# misc_sensors.net
KiCad netlist of a schematic drawn in Altium Designer
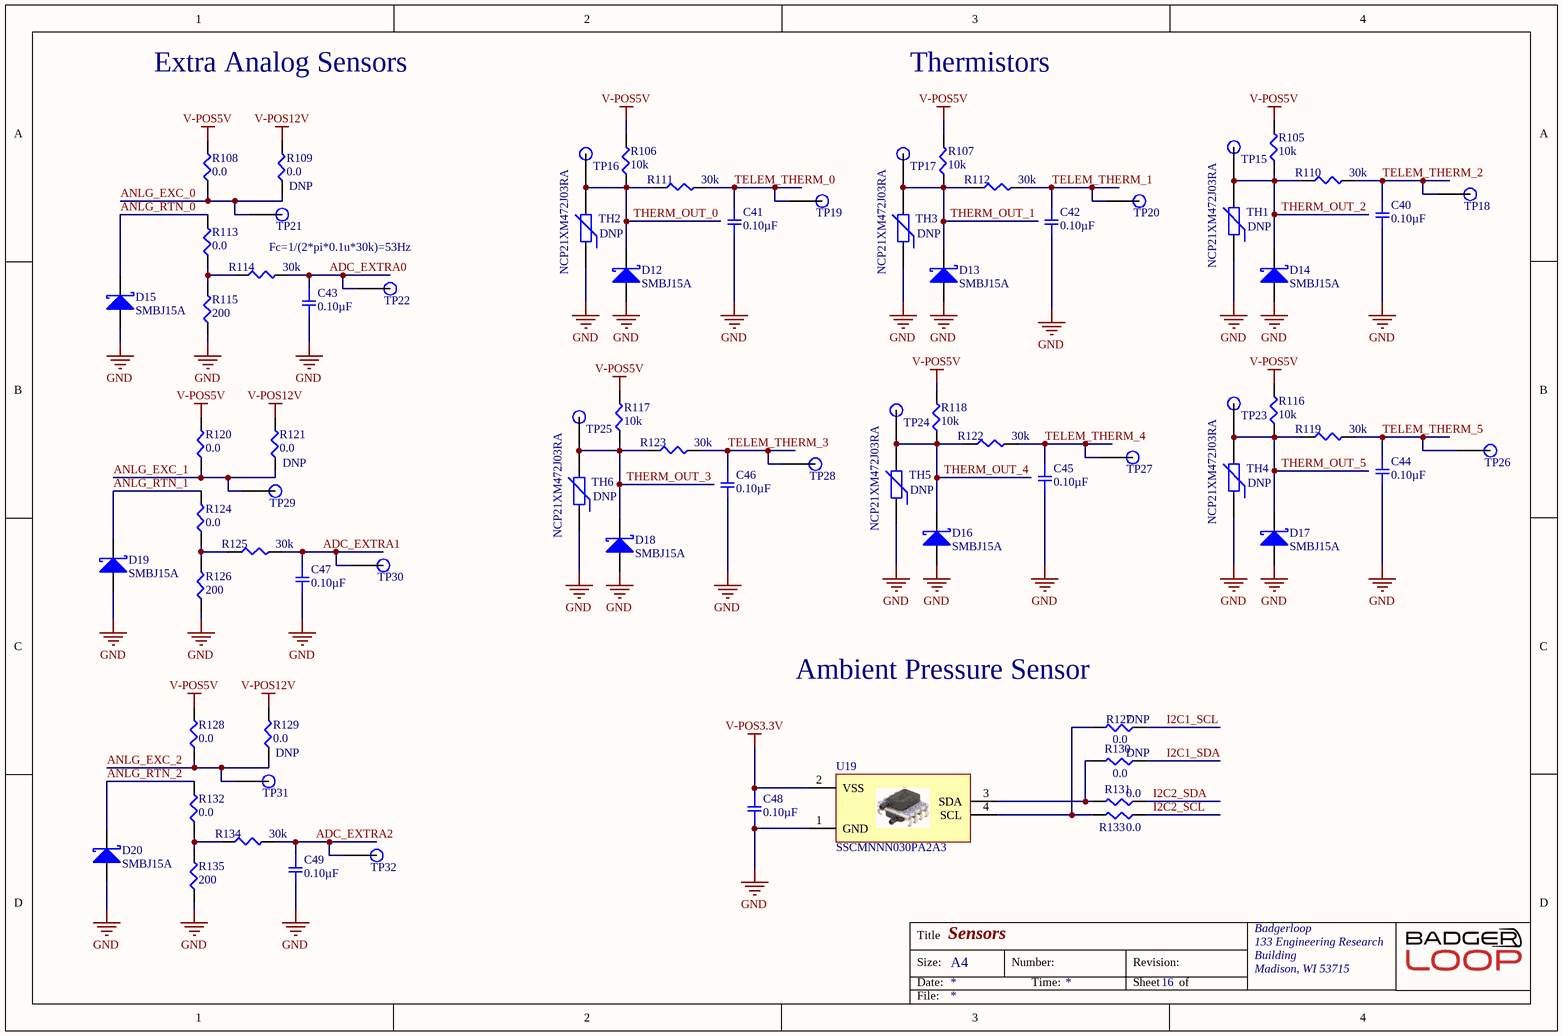
[diagram p0: misc_sensors.SchDoc]

(export (version "E")
  (design (tool "Eeschema 10.0.6"))
  (components
    (comp (ref "C40")
      (value "0.10µF")
      (footprint "SMD-0805C")
      (description "CAP CER 0.1UF 16V X7R 0805")
      (fields
        (field (name "DIGI-KEY PART NUMBER") "490-1683-1-ND")
        (field (name "PART NUMBER") "GRM219R71C104KA01D")
      )
      (libsource (lib "capacitors") (part "GRM219R71C104KA01D"))
    )
    (comp (ref "C41")
      (value "0.10µF")
      (footprint "SMD-0805C")
      (description "CAP CER 0.1UF 16V X7R 0805")
      (fields
        (field (name "DIGI-KEY PART NUMBER") "490-1683-1-ND")
        (field (name "PART NUMBER") "GRM219R71C104KA01D")
      )
      (libsource (lib "capacitors") (part "GRM219R71C104KA01D"))
    )
    (comp (ref "C42")
      (value "0.10µF")
      (footprint "SMD-0805C")
      (description "CAP CER 0.1UF 16V X7R 0805")
      (fields
        (field (name "DIGI-KEY PART NUMBER") "490-1683-1-ND")
        (field (name "PART NUMBER") "GRM219R71C104KA01D")
      )
      (libsource (lib "capacitors") (part "GRM219R71C104KA01D"))
    )
    (comp (ref "C43")
      (value "0.10µF")
      (footprint "SMD-0805C")
      (description "CAP CER 0.1UF 25V X7R 0805")
      (fields
        (field (name "DIGI-KEY PART NUMBER") "490-12754-1-ND")
        (field (name "PART NUMBER") "GRM219R71E104KA01D")
      )
      (libsource (lib "capacitors") (part "GRM219R71E104KA01D"))
    )
    (comp (ref "C44")
      (value "0.10µF")
      (footprint "SMD-0805C")
      (description "CAP CER 0.1UF 16V X7R 0805")
      (fields
        (field (name "DIGI-KEY PART NUMBER") "490-1683-1-ND")
        (field (name "PART NUMBER") "GRM219R71C104KA01D")
      )
      (libsource (lib "capacitors") (part "GRM219R71C104KA01D"))
    )
    (comp (ref "C45")
      (value "0.10µF")
      (footprint "SMD-0805C")
      (description "CAP CER 0.1UF 16V X7R 0805")
      (fields
        (field (name "DIGI-KEY PART NUMBER") "490-1683-1-ND")
        (field (name "PART NUMBER") "GRM219R71C104KA01D")
      )
      (libsource (lib "capacitors") (part "GRM219R71C104KA01D"))
    )
    (comp (ref "C46")
      (value "0.10µF")
      (footprint "SMD-0805C")
      (description "CAP CER 0.1UF 16V X7R 0805")
      (fields
        (field (name "DIGI-KEY PART NUMBER") "490-1683-1-ND")
        (field (name "PART NUMBER") "GRM219R71C104KA01D")
      )
      (libsource (lib "capacitors") (part "GRM219R71C104KA01D"))
    )
    (comp (ref "C47")
      (value "0.10µF")
      (footprint "SMD-0805C")
      (description "CAP CER 0.1UF 25V X7R 0805")
      (fields
        (field (name "DIGI-KEY PART NUMBER") "490-12754-1-ND")
        (field (name "PART NUMBER") "GRM219R71E104KA01D")
      )
      (libsource (lib "capacitors") (part "GRM219R71E104KA01D"))
    )
    (comp (ref "C48")
      (value "0.10µF")
      (footprint "SMD-0805C")
      (description "CAP CER 0.1UF 25V X7R 0805")
      (fields
        (field (name "DIGI-KEY PART NUMBER") "490-12754-1-ND")
        (field (name "PART NUMBER") "GRM219R71E104KA01D")
      )
      (libsource (lib "capacitors") (part "GRM219R71E104KA01D"))
    )
    (comp (ref "C49")
      (value "0.10µF")
      (footprint "SMD-0805C")
      (description "CAP CER 0.1UF 25V X7R 0805")
      (fields
        (field (name "DIGI-KEY PART NUMBER") "490-12754-1-ND")
        (field (name "PART NUMBER") "GRM219R71E104KA01D")
      )
      (libsource (lib "capacitors") (part "GRM219R71E104KA01D"))
    )
    (comp (ref "D12")
      (value "SMBJ15A")
      (footprint "DIOM4436X26N")
      (description "TVS DIODE 15V 24.4V DO214AA")
      (fields (field (name "MANUFACTURER") "Littelfuse") (field (name "VOLTAGE") "5V"))
      (libsource (lib "misc") (part "SMBJ15A"))
    )
    (comp (ref "D13")
      (value "SMBJ15A")
      (footprint "DIOM4436X26N")
      (description "TVS DIODE 15V 24.4V DO214AA")
      (fields (field (name "MANUFACTURER") "Littelfuse") (field (name "VOLTAGE") "5V"))
      (libsource (lib "misc") (part "SMBJ15A"))
    )
    (comp (ref "D14")
      (value "SMBJ15A")
      (footprint "DIOM4436X26N")
      (description "TVS DIODE 15V 24.4V DO214AA")
      (fields (field (name "MANUFACTURER") "Littelfuse") (field (name "VOLTAGE") "5V"))
      (libsource (lib "misc") (part "SMBJ15A"))
    )
    (comp (ref "D15")
      (value "SMBJ15A")
      (footprint "DIOM4436X26N")
      (description "TVS DIODE 15V 24.4V DO214AA")
      (fields (field (name "MANUFACTURER") "Littelfuse") (field (name "VOLTAGE") "5V"))
      (libsource (lib "misc") (part "SMBJ15A"))
    )
    (comp (ref "D16")
      (value "SMBJ15A")
      (footprint "DIOM4436X26N")
      (description "TVS DIODE 15V 24.4V DO214AA")
      (fields (field (name "MANUFACTURER") "Littelfuse") (field (name "VOLTAGE") "5V"))
      (libsource (lib "misc") (part "SMBJ15A"))
    )
    (comp (ref "D17")
      (value "SMBJ15A")
      (footprint "DIOM4436X26N")
      (description "TVS DIODE 15V 24.4V DO214AA")
      (fields (field (name "MANUFACTURER") "Littelfuse") (field (name "VOLTAGE") "5V"))
      (libsource (lib "misc") (part "SMBJ15A"))
    )
    (comp (ref "D18")
      (value "SMBJ15A")
      (footprint "DIOM4436X26N")
      (description "TVS DIODE 15V 24.4V DO214AA")
      (fields (field (name "MANUFACTURER") "Littelfuse") (field (name "VOLTAGE") "5V"))
      (libsource (lib "misc") (part "SMBJ15A"))
    )
    (comp (ref "D19")
      (value "SMBJ15A")
      (footprint "DIOM4436X26N")
      (description "TVS DIODE 15V 24.4V DO214AA")
      (fields (field (name "MANUFACTURER") "Littelfuse") (field (name "VOLTAGE") "5V"))
      (libsource (lib "misc") (part "SMBJ15A"))
    )
    (comp (ref "D20")
      (value "SMBJ15A")
      (footprint "DIOM4436X26N")
      (description "TVS DIODE 15V 24.4V DO214AA")
      (fields (field (name "MANUFACTURER") "Littelfuse") (field (name "VOLTAGE") "5V"))
      (libsource (lib "misc") (part "SMBJ15A"))
    )
    (comp (ref "R105")
      (value "10k")
      (footprint "SMD-0805-RES")
      (description "RES SMD 10K OHM 1% 1/2W 0805")
      (fields
        (field (name "PART NUMBER") "ERJ-P06F1002V")
        (field (name "DIGI-KEY PART NUMBER") "P16059CT-ND")
      )
      (libsource (lib "resistors") (part "ERJ-P06F1002V"))
    )
    (comp (ref "R106")
      (value "10k")
      (footprint "SMD-0805-RES")
      (description "RES SMD 10K OHM 1% 1/2W 0805")
      (fields
        (field (name "PART NUMBER") "ERJ-P06F1002V")
        (field (name "DIGI-KEY PART NUMBER") "P16059CT-ND")
      )
      (libsource (lib "resistors") (part "ERJ-P06F1002V"))
    )
    (comp (ref "R107")
      (value "10k")
      (footprint "SMD-0805-RES")
      (description "RES SMD 10K OHM 1% 1/2W 0805")
      (fields
        (field (name "PART NUMBER") "ERJ-P06F1002V")
        (field (name "DIGI-KEY PART NUMBER") "P16059CT-ND")
      )
      (libsource (lib "resistors") (part "ERJ-P06F1002V"))
    )
    (comp (ref "R108")
      (value "0.0")
      (footprint "SMD-0805-RES")
      (description "RES SMD 0.0 OHM JUMPER 1/8W 0805")
      (fields (field (name "PART NUMBER") "ERJ-6GEY0R00V") (field (name "DIGI-KEY PART NUMBER") "P0.0ACT-ND"))
      (libsource (lib "resistors") (part "ERJ-6GEY0R00V"))
    )
    (comp (ref "R109")
      (value "0.0")
      (footprint "SMD-0805-RES")
      (description "RES SMD 0.0 OHM JUMPER 1/8W 0805")
      (fields
        (field (name "PART NUMBER") "ERJ-6GEY0R00V")
        (field (name "DIGI-KEY PART NUMBER") "P0.0ACT-ND")
        (field (name "DNP") "DNP")
      )
      (libsource (lib "resistors") (part "ERJ-6GEY0R00V"))
    )
    (comp (ref "R110")
      (value "30k")
      (footprint "SMD-0805-RES")
      (description "RES SMD 30K OHM 1% 1/8W 0805")
      (fields
        (field (name "PART NUMBER") "ERJ-6ENF3002V")
        (field (name "DIGI-KEY PART NUMBER") "P30.0KCCT-ND")
      )
      (libsource (lib "resistors") (part "ERJ-6ENF3002V"))
    )
    (comp (ref "R111")
      (value "30k")
      (footprint "SMD-0805-RES")
      (description "RES SMD 30K OHM 1% 1/8W 0805")
      (fields
        (field (name "PART NUMBER") "ERJ-6ENF3002V")
        (field (name "DIGI-KEY PART NUMBER") "P30.0KCCT-ND")
      )
      (libsource (lib "resistors") (part "ERJ-6ENF3002V"))
    )
    (comp (ref "R112")
      (value "30k")
      (footprint "SMD-0805-RES")
      (description "RES SMD 30K OHM 1% 1/8W 0805")
      (fields
        (field (name "PART NUMBER") "ERJ-6ENF3002V")
        (field (name "DIGI-KEY PART NUMBER") "P30.0KCCT-ND")
      )
      (libsource (lib "resistors") (part "ERJ-6ENF3002V"))
    )
    (comp (ref "R113")
      (value "0.0")
      (footprint "SMD-0805-RES")
      (description "RES SMD 0.0 OHM JUMPER 1/8W 0805")
      (fields (field (name "PART NUMBER") "ERJ-6GEY0R00V") (field (name "DIGI-KEY PART NUMBER") "P0.0ACT-ND"))
      (libsource (lib "resistors") (part "ERJ-6GEY0R00V"))
    )
    (comp (ref "R114")
      (value "30k")
      (footprint "SMD-0805-RES")
      (description "RES SMD 30K OHM 1% 1/8W 0805")
      (fields
        (field (name "PART NUMBER") "ERJ-6ENF3002V")
        (field (name "DIGI-KEY PART NUMBER") "P30.0KCCT-ND")
      )
      (libsource (lib "resistors") (part "ERJ-6ENF3002V"))
    )
    (comp (ref "R115")
      (value "200")
      (footprint "SMD-0805-RES")
      (description "RES SMD 200 OHM 1% 1/2W 0805")
      (fields
        (field (name "PART NUMBER") "ERJ-P06F2000V")
        (field (name "DIGI-KEY PART NUMBER") "P16064CT-ND")
      )
      (libsource (lib "resistors") (part "ERJ-P06F2000V"))
    )
    (comp (ref "R116")
      (value "10k")
      (footprint "SMD-0805-RES")
      (description "RES SMD 10K OHM 1% 1/2W 0805")
      (fields
        (field (name "PART NUMBER") "ERJ-P06F1002V")
        (field (name "DIGI-KEY PART NUMBER") "P16059CT-ND")
      )
      (libsource (lib "resistors") (part "ERJ-P06F1002V"))
    )
    (comp (ref "R117")
      (value "10k")
      (footprint "SMD-0805-RES")
      (description "RES SMD 10K OHM 1% 1/2W 0805")
      (fields
        (field (name "PART NUMBER") "ERJ-P06F1002V")
        (field (name "DIGI-KEY PART NUMBER") "P16059CT-ND")
      )
      (libsource (lib "resistors") (part "ERJ-P06F1002V"))
    )
    (comp (ref "R118")
      (value "10k")
      (footprint "SMD-0805-RES")
      (description "RES SMD 10K OHM 1% 1/2W 0805")
      (fields
        (field (name "PART NUMBER") "ERJ-P06F1002V")
        (field (name "DIGI-KEY PART NUMBER") "P16059CT-ND")
      )
      (libsource (lib "resistors") (part "ERJ-P06F1002V"))
    )
    (comp (ref "R119")
      (value "30k")
      (footprint "SMD-0805-RES")
      (description "RES SMD 30K OHM 1% 1/8W 0805")
      (fields
        (field (name "PART NUMBER") "ERJ-6ENF3002V")
        (field (name "DIGI-KEY PART NUMBER") "P30.0KCCT-ND")
      )
      (libsource (lib "resistors") (part "ERJ-6ENF3002V"))
    )
    (comp (ref "R120")
      (value "0.0")
      (footprint "SMD-0805-RES")
      (description "RES SMD 0.0 OHM JUMPER 1/8W 0805")
      (fields (field (name "PART NUMBER") "ERJ-6GEY0R00V") (field (name "DIGI-KEY PART NUMBER") "P0.0ACT-ND"))
      (libsource (lib "resistors") (part "ERJ-6GEY0R00V"))
    )
    (comp (ref "R121")
      (value "0.0")
      (footprint "SMD-0805-RES")
      (description "RES SMD 0.0 OHM JUMPER 1/8W 0805")
      (fields
        (field (name "PART NUMBER") "ERJ-6GEY0R00V")
        (field (name "DIGI-KEY PART NUMBER") "P0.0ACT-ND")
        (field (name "DNP") "DNP")
      )
      (libsource (lib "resistors") (part "ERJ-6GEY0R00V"))
    )
    (comp (ref "R122")
      (value "30k")
      (footprint "SMD-0805-RES")
      (description "RES SMD 30K OHM 1% 1/8W 0805")
      (fields
        (field (name "PART NUMBER") "ERJ-6ENF3002V")
        (field (name "DIGI-KEY PART NUMBER") "P30.0KCCT-ND")
      )
      (libsource (lib "resistors") (part "ERJ-6ENF3002V"))
    )
    (comp (ref "R123")
      (value "30k")
      (footprint "SMD-0805-RES")
      (description "RES SMD 30K OHM 1% 1/8W 0805")
      (fields
        (field (name "PART NUMBER") "ERJ-6ENF3002V")
        (field (name "DIGI-KEY PART NUMBER") "P30.0KCCT-ND")
      )
      (libsource (lib "resistors") (part "ERJ-6ENF3002V"))
    )
    (comp (ref "R124")
      (value "0.0")
      (footprint "SMD-0805-RES")
      (description "RES SMD 0.0 OHM JUMPER 1/8W 0805")
      (fields (field (name "PART NUMBER") "ERJ-6GEY0R00V") (field (name "DIGI-KEY PART NUMBER") "P0.0ACT-ND"))
      (libsource (lib "resistors") (part "ERJ-6GEY0R00V"))
    )
    (comp (ref "R125")
      (value "30k")
      (footprint "SMD-0805-RES")
      (description "RES SMD 30K OHM 1% 1/8W 0805")
      (fields
        (field (name "PART NUMBER") "ERJ-6ENF3002V")
        (field (name "DIGI-KEY PART NUMBER") "P30.0KCCT-ND")
      )
      (libsource (lib "resistors") (part "ERJ-6ENF3002V"))
    )
    (comp (ref "R126")
      (value "200")
      (footprint "SMD-0805-RES")
      (description "RES SMD 200 OHM 1% 1/2W 0805")
      (fields
        (field (name "PART NUMBER") "ERJ-P06F2000V")
        (field (name "DIGI-KEY PART NUMBER") "P16064CT-ND")
      )
      (libsource (lib "resistors") (part "ERJ-P06F2000V"))
    )
    (comp (ref "R127")
      (value "0.0")
      (footprint "SMD-0805-RES")
      (description "RES SMD 0.0 OHM JUMPER 1/8W 0805")
      (fields
        (field (name "PART NUMBER") "ERJ-6GEY0R00V")
        (field (name "DIGI-KEY PART NUMBER") "P0.0ACT-ND")
        (field (name "DNP") "DNP")
      )
      (libsource (lib "resistors") (part "ERJ-6GEY0R00V"))
    )
    (comp (ref "R128")
      (value "0.0")
      (footprint "SMD-0805-RES")
      (description "RES SMD 0.0 OHM JUMPER 1/8W 0805")
      (fields (field (name "PART NUMBER") "ERJ-6GEY0R00V") (field (name "DIGI-KEY PART NUMBER") "P0.0ACT-ND"))
      (libsource (lib "resistors") (part "ERJ-6GEY0R00V"))
    )
    (comp (ref "R129")
      (value "0.0")
      (footprint "SMD-0805-RES")
      (description "RES SMD 0.0 OHM JUMPER 1/8W 0805")
      (fields
        (field (name "PART NUMBER") "ERJ-6GEY0R00V")
        (field (name "DIGI-KEY PART NUMBER") "P0.0ACT-ND")
        (field (name "DNP") "DNP")
      )
      (libsource (lib "resistors") (part "ERJ-6GEY0R00V"))
    )
    (comp (ref "R130")
      (value "0.0")
      (footprint "SMD-0805-RES")
      (description "RES SMD 0.0 OHM JUMPER 1/8W 0805")
      (fields
        (field (name "PART NUMBER") "ERJ-6GEY0R00V")
        (field (name "DIGI-KEY PART NUMBER") "P0.0ACT-ND")
        (field (name "DNP") "DNP")
      )
      (libsource (lib "resistors") (part "ERJ-6GEY0R00V"))
    )
    (comp (ref "R131")
      (value "0.0")
      (footprint "SMD-0805-RES")
      (description "RES SMD 0.0 OHM JUMPER 1/8W 0805")
      (fields (field (name "PART NUMBER") "ERJ-6GEY0R00V") (field (name "DIGI-KEY PART NUMBER") "P0.0ACT-ND"))
      (libsource (lib "resistors") (part "ERJ-6GEY0R00V"))
    )
    (comp (ref "R132")
      (value "0.0")
      (footprint "SMD-0805-RES")
      (description "RES SMD 0.0 OHM JUMPER 1/8W 0805")
      (fields (field (name "PART NUMBER") "ERJ-6GEY0R00V") (field (name "DIGI-KEY PART NUMBER") "P0.0ACT-ND"))
      (libsource (lib "resistors") (part "ERJ-6GEY0R00V"))
    )
    (comp (ref "R133")
      (value "0.0")
      (footprint "SMD-0805-RES")
      (description "RES SMD 0.0 OHM JUMPER 1/8W 0805")
      (fields (field (name "PART NUMBER") "ERJ-6GEY0R00V") (field (name "DIGI-KEY PART NUMBER") "P0.0ACT-ND"))
      (libsource (lib "resistors") (part "ERJ-6GEY0R00V"))
    )
    (comp (ref "R134")
      (value "30k")
      (footprint "SMD-0805-RES")
      (description "RES SMD 30K OHM 1% 1/8W 0805")
      (fields
        (field (name "PART NUMBER") "ERJ-6ENF3002V")
        (field (name "DIGI-KEY PART NUMBER") "P30.0KCCT-ND")
      )
      (libsource (lib "resistors") (part "ERJ-6ENF3002V"))
    )
    (comp (ref "R135")
      (value "200")
      (footprint "SMD-0805-RES")
      (description "RES SMD 200 OHM 1% 1/2W 0805")
      (fields
        (field (name "PART NUMBER") "ERJ-P06F2000V")
        (field (name "DIGI-KEY PART NUMBER") "P16064CT-ND")
      )
      (libsource (lib "resistors") (part "ERJ-P06F2000V"))
    )
    (comp (ref "TH1")
      (value "NCP21XM472J03RA")
      (footprint "SMD-0805-RES")
      (description "NTC THERMISTOR 4.7K OHM 5% 0805")
      (fields
        (field (name "MANUFACTURER") "Murata")
        (field (name "TOLERANCE") "5%")
        (field (name "DNP") "DNP")
      )
      (libsource (lib "misc") (part "NCP21XM472J03RA"))
    )
    (comp (ref "TH2")
      (value "NCP21XM472J03RA")
      (footprint "SMD-0805-RES")
      (description "NTC THERMISTOR 4.7K OHM 5% 0805")
      (fields
        (field (name "MANUFACTURER") "Murata")
        (field (name "TOLERANCE") "5%")
        (field (name "DNP") "DNP")
      )
      (libsource (lib "misc") (part "NCP21XM472J03RA"))
    )
    (comp (ref "TH3")
      (value "NCP21XM472J03RA")
      (footprint "SMD-0805-RES")
      (description "NTC THERMISTOR 4.7K OHM 5% 0805")
      (fields
        (field (name "MANUFACTURER") "Murata")
        (field (name "TOLERANCE") "5%")
        (field (name "DNP") "DNP")
      )
      (libsource (lib "misc") (part "NCP21XM472J03RA"))
    )
    (comp (ref "TH4")
      (value "NCP21XM472J03RA")
      (footprint "SMD-0805-RES")
      (description "NTC THERMISTOR 4.7K OHM 5% 0805")
      (fields
        (field (name "MANUFACTURER") "Murata")
        (field (name "TOLERANCE") "5%")
        (field (name "DNP") "DNP")
      )
      (libsource (lib "misc") (part "NCP21XM472J03RA"))
    )
    (comp (ref "TH5")
      (value "NCP21XM472J03RA")
      (footprint "SMD-0805-RES")
      (description "NTC THERMISTOR 4.7K OHM 5% 0805")
      (fields
        (field (name "MANUFACTURER") "Murata")
        (field (name "TOLERANCE") "5%")
        (field (name "DNP") "DNP")
      )
      (libsource (lib "misc") (part "NCP21XM472J03RA"))
    )
    (comp (ref "TH6")
      (value "NCP21XM472J03RA")
      (footprint "SMD-0805-RES")
      (description "NTC THERMISTOR 4.7K OHM 5% 0805")
      (fields
        (field (name "MANUFACTURER") "Murata")
        (field (name "TOLERANCE") "5%")
        (field (name "DNP") "DNP")
      )
      (libsource (lib "misc") (part "NCP21XM472J03RA"))
    )
    (comp (ref "TP15")
      (value "TP")
      (footprint "Test Point")
      (description "SMD TEST POINT")
      (libsource (lib "misc") (part "TP"))
    )
    (comp (ref "TP16")
      (value "TP")
      (footprint "Test Point")
      (description "SMD TEST POINT")
      (libsource (lib "misc") (part "TP"))
    )
    (comp (ref "TP17")
      (value "TP")
      (footprint "Test Point")
      (description "SMD TEST POINT")
      (libsource (lib "misc") (part "TP"))
    )
    (comp (ref "TP18")
      (value "TP")
      (footprint "Test Point")
      (description "SMD TEST POINT")
      (libsource (lib "misc") (part "TP"))
    )
    (comp (ref "TP19")
      (value "TP")
      (footprint "Test Point")
      (description "SMD TEST POINT")
      (libsource (lib "misc") (part "TP"))
    )
    (comp (ref "TP20")
      (value "TP")
      (footprint "Test Point")
      (description "SMD TEST POINT")
      (libsource (lib "misc") (part "TP"))
    )
    (comp (ref "TP21")
      (value "TP")
      (footprint "Test Point")
      (description "SMD TEST POINT")
      (libsource (lib "misc") (part "TP"))
    )
    (comp (ref "TP22")
      (value "TP")
      (footprint "Test Point")
      (description "SMD TEST POINT")
      (libsource (lib "misc") (part "TP"))
    )
    (comp (ref "TP23")
      (value "TP")
      (footprint "Test Point")
      (description "SMD TEST POINT")
      (libsource (lib "misc") (part "TP"))
    )
    (comp (ref "TP24")
      (value "TP")
      (footprint "Test Point")
      (description "SMD TEST POINT")
      (libsource (lib "misc") (part "TP"))
    )
    (comp (ref "TP25")
      (value "TP")
      (footprint "Test Point")
      (description "SMD TEST POINT")
      (libsource (lib "misc") (part "TP"))
    )
    (comp (ref "TP26")
      (value "TP")
      (footprint "Test Point")
      (description "SMD TEST POINT")
      (libsource (lib "misc") (part "TP"))
    )
    (comp (ref "TP27")
      (value "TP")
      (footprint "Test Point")
      (description "SMD TEST POINT")
      (libsource (lib "misc") (part "TP"))
    )
    (comp (ref "TP28")
      (value "TP")
      (footprint "Test Point")
      (description "SMD TEST POINT")
      (libsource (lib "misc") (part "TP"))
    )
    (comp (ref "TP29")
      (value "TP")
      (footprint "Test Point")
      (description "SMD TEST POINT")
      (libsource (lib "misc") (part "TP"))
    )
    (comp (ref "TP30")
      (value "TP")
      (footprint "Test Point")
      (description "SMD TEST POINT")
      (libsource (lib "misc") (part "TP"))
    )
    (comp (ref "TP31")
      (value "TP")
      (footprint "Test Point")
      (description "SMD TEST POINT")
      (libsource (lib "misc") (part "TP"))
    )
    (comp (ref "TP32")
      (value "TP")
      (footprint "Test Point")
      (description "SMD TEST POINT")
      (libsource (lib "misc") (part "TP"))
    )
    (comp (ref "U19")
      (value "SSCMNNN030PA2A3")
      (footprint "8-SMT")
      (description "Honeywell Digital Pressure Sensor")
      (libsource (lib "ic") (part "SSCMNNN030PA2A3"))
    )
  )
  (nets
    (net (code "1") (name "/ADC_EXTRA0") (class "Default")
      (node (ref "C43") (pin "1") (pinfunction "1_1") (pintype "passive"))
      (node (ref "R114") (pin "2") (pinfunction "2_2") (pintype "passive"))
      (node (ref "TP22") (pin "1") (pinfunction "1_1") (pintype "passive"))
    )
    (net (code "2") (name "/ADC_EXTRA1") (class "Default")
      (node (ref "C47") (pin "1") (pinfunction "1_1") (pintype "passive"))
      (node (ref "R125") (pin "2") (pinfunction "2_2") (pintype "passive"))
      (node (ref "TP30") (pin "1") (pinfunction "1_1") (pintype "passive"))
    )
    (net (code "3") (name "/ADC_EXTRA2") (class "Default")
      (node (ref "C49") (pin "1") (pinfunction "1_1") (pintype "passive"))
      (node (ref "R134") (pin "2") (pinfunction "2_2") (pintype "passive"))
      (node (ref "TP32") (pin "1") (pinfunction "1_1") (pintype "passive"))
    )
    (net (code "4") (name "/ANLG_EXC_0") (class "Default")
      (node (ref "R108") (pin "1") (pinfunction "1_1") (pintype "passive"))
      (node (ref "R109") (pin "1") (pinfunction "1_1") (pintype "passive"))
      (node (ref "TP21") (pin "1") (pinfunction "1_1") (pintype "passive"))
    )
    (net (code "5") (name "/ANLG_EXC_1") (class "Default")
      (node (ref "R120") (pin "1") (pinfunction "1_1") (pintype "passive"))
      (node (ref "R121") (pin "1") (pinfunction "1_1") (pintype "passive"))
      (node (ref "TP29") (pin "1") (pinfunction "1_1") (pintype "passive"))
    )
    (net (code "6") (name "/ANLG_EXC_2") (class "Default")
      (node (ref "R128") (pin "1") (pinfunction "1_1") (pintype "passive"))
      (node (ref "R129") (pin "1") (pinfunction "1_1") (pintype "passive"))
      (node (ref "TP31") (pin "1") (pinfunction "1_1") (pintype "passive"))
    )
    (net (code "7") (name "/ANLG_RTN_0") (class "Default")
      (node (ref "D15") (pin "1") (pinfunction "A_1") (pintype "passive"))
      (node (ref "R113") (pin "2") (pinfunction "2_2") (pintype "passive"))
    )
    (net (code "8") (name "/ANLG_RTN_1") (class "Default")
      (node (ref "D19") (pin "1") (pinfunction "A_1") (pintype "passive"))
      (node (ref "R124") (pin "2") (pinfunction "2_2") (pintype "passive"))
    )
    (net (code "9") (name "/ANLG_RTN_2") (class "Default")
      (node (ref "D20") (pin "1") (pinfunction "A_1") (pintype "passive"))
      (node (ref "R132") (pin "2") (pinfunction "2_2") (pintype "passive"))
    )
    (net (code "10") (name "/I2C1_SCL") (class "Default")
      (node (ref "R127") (pin "1") (pinfunction "1_1") (pintype "passive"))
    )
    (net (code "11") (name "/I2C1_SDA") (class "Default")
      (node (ref "R130") (pin "1") (pinfunction "1_1") (pintype "passive"))
    )
    (net (code "12") (name "/I2C2_SCL") (class "Default")
      (node (ref "R133") (pin "1") (pinfunction "1_1") (pintype "passive"))
    )
    (net (code "13") (name "/I2C2_SDA") (class "Default")
      (node (ref "R131") (pin "1") (pinfunction "1_1") (pintype "passive"))
    )
    (net (code "14") (name "/TELEM_THERM_0") (class "Default")
      (node (ref "C41") (pin "1") (pinfunction "1_1") (pintype "passive"))
      (node (ref "R111") (pin "2") (pinfunction "2_2") (pintype "passive"))
      (node (ref "TP19") (pin "1") (pinfunction "1_1") (pintype "passive"))
    )
    (net (code "15") (name "/TELEM_THERM_1") (class "Default")
      (node (ref "C42") (pin "1") (pinfunction "1_1") (pintype "passive"))
      (node (ref "R112") (pin "2") (pinfunction "2_2") (pintype "passive"))
      (node (ref "TP20") (pin "1") (pinfunction "1_1") (pintype "passive"))
    )
    (net (code "16") (name "/TELEM_THERM_2") (class "Default")
      (node (ref "C40") (pin "1") (pinfunction "1_1") (pintype "passive"))
      (node (ref "R110") (pin "2") (pinfunction "2_2") (pintype "passive"))
      (node (ref "TP18") (pin "1") (pinfunction "1_1") (pintype "passive"))
    )
    (net (code "17") (name "/TELEM_THERM_3") (class "Default")
      (node (ref "C46") (pin "1") (pinfunction "1_1") (pintype "passive"))
      (node (ref "R123") (pin "2") (pinfunction "2_2") (pintype "passive"))
      (node (ref "TP28") (pin "1") (pinfunction "1_1") (pintype "passive"))
    )
    (net (code "18") (name "/TELEM_THERM_4") (class "Default")
      (node (ref "C45") (pin "1") (pinfunction "1_1") (pintype "passive"))
      (node (ref "R122") (pin "2") (pinfunction "2_2") (pintype "passive"))
      (node (ref "TP27") (pin "1") (pinfunction "1_1") (pintype "passive"))
    )
    (net (code "19") (name "/TELEM_THERM_5") (class "Default")
      (node (ref "C44") (pin "1") (pinfunction "1_1") (pintype "passive"))
      (node (ref "R119") (pin "2") (pinfunction "2_2") (pintype "passive"))
      (node (ref "TP26") (pin "1") (pinfunction "1_1") (pintype "passive"))
    )
    (net (code "20") (name "/THERM_OUT_0") (class "Default")
      (node (ref "D12") (pin "1") (pinfunction "A_1") (pintype "passive"))
      (node (ref "R106") (pin "1") (pinfunction "1_1") (pintype "passive"))
      (node (ref "R111") (pin "1") (pinfunction "1_1") (pintype "passive"))
      (node (ref "TH2") (pin "2") (pinfunction "2_2") (pintype "passive"))
      (node (ref "TP16") (pin "1") (pinfunction "1_1") (pintype "passive"))
    )
    (net (code "21") (name "/THERM_OUT_1") (class "Default")
      (node (ref "D13") (pin "1") (pinfunction "A_1") (pintype "passive"))
      (node (ref "R107") (pin "1") (pinfunction "1_1") (pintype "passive"))
      (node (ref "R112") (pin "1") (pinfunction "1_1") (pintype "passive"))
      (node (ref "TH3") (pin "2") (pinfunction "2_2") (pintype "passive"))
      (node (ref "TP17") (pin "1") (pinfunction "1_1") (pintype "passive"))
    )
    (net (code "22") (name "/THERM_OUT_2") (class "Default")
      (node (ref "D14") (pin "1") (pinfunction "A_1") (pintype "passive"))
      (node (ref "R105") (pin "1") (pinfunction "1_1") (pintype "passive"))
      (node (ref "R110") (pin "1") (pinfunction "1_1") (pintype "passive"))
      (node (ref "TH1") (pin "2") (pinfunction "2_2") (pintype "passive"))
      (node (ref "TP15") (pin "1") (pinfunction "1_1") (pintype "passive"))
    )
    (net (code "23") (name "/THERM_OUT_3") (class "Default")
      (node (ref "D18") (pin "1") (pinfunction "A_1") (pintype "passive"))
      (node (ref "R117") (pin "1") (pinfunction "1_1") (pintype "passive"))
      (node (ref "R123") (pin "1") (pinfunction "1_1") (pintype "passive"))
      (node (ref "TH6") (pin "2") (pinfunction "2_2") (pintype "passive"))
      (node (ref "TP25") (pin "1") (pinfunction "1_1") (pintype "passive"))
    )
    (net (code "24") (name "/THERM_OUT_4") (class "Default")
      (node (ref "D16") (pin "1") (pinfunction "A_1") (pintype "passive"))
      (node (ref "R118") (pin "1") (pinfunction "1_1") (pintype "passive"))
      (node (ref "R122") (pin "1") (pinfunction "1_1") (pintype "passive"))
      (node (ref "TH5") (pin "2") (pinfunction "2_2") (pintype "passive"))
      (node (ref "TP24") (pin "1") (pinfunction "1_1") (pintype "passive"))
    )
    (net (code "25") (name "/THERM_OUT_5") (class "Default")
      (node (ref "D17") (pin "1") (pinfunction "A_1") (pintype "passive"))
      (node (ref "R116") (pin "1") (pinfunction "1_1") (pintype "passive"))
      (node (ref "R119") (pin "1") (pinfunction "1_1") (pintype "passive"))
      (node (ref "TH4") (pin "2") (pinfunction "2_2") (pintype "passive"))
      (node (ref "TP23") (pin "1") (pinfunction "1_1") (pintype "passive"))
    )
    (net (code "26") (name "GND") (class "Default")
      (node (ref "C40") (pin "2") (pinfunction "2_2") (pintype "passive"))
      (node (ref "C41") (pin "2") (pinfunction "2_2") (pintype "passive"))
      (node (ref "C42") (pin "2") (pinfunction "2_2") (pintype "passive"))
      (node (ref "C43") (pin "2") (pinfunction "2_2") (pintype "passive"))
      (node (ref "C44") (pin "2") (pinfunction "2_2") (pintype "passive"))
      (node (ref "C45") (pin "2") (pinfunction "2_2") (pintype "passive"))
      (node (ref "C46") (pin "2") (pinfunction "2_2") (pintype "passive"))
      (node (ref "C47") (pin "2") (pinfunction "2_2") (pintype "passive"))
      (node (ref "C48") (pin "2") (pinfunction "2_2") (pintype "passive"))
      (node (ref "C49") (pin "2") (pinfunction "2_2") (pintype "passive"))
      (node (ref "D12") (pin "2") (pinfunction "K_2") (pintype "passive"))
      (node (ref "D13") (pin "2") (pinfunction "K_2") (pintype "passive"))
      (node (ref "D14") (pin "2") (pinfunction "K_2") (pintype "passive"))
      (node (ref "D15") (pin "2") (pinfunction "K_2") (pintype "passive"))
      (node (ref "D16") (pin "2") (pinfunction "K_2") (pintype "passive"))
      (node (ref "D17") (pin "2") (pinfunction "K_2") (pintype "passive"))
      (node (ref "D18") (pin "2") (pinfunction "K_2") (pintype "passive"))
      (node (ref "D19") (pin "2") (pinfunction "K_2") (pintype "passive"))
      (node (ref "D20") (pin "2") (pinfunction "K_2") (pintype "passive"))
      (node (ref "R115") (pin "1") (pinfunction "1_1") (pintype "passive"))
      (node (ref "R126") (pin "1") (pinfunction "1_1") (pintype "passive"))
      (node (ref "R135") (pin "1") (pinfunction "1_1") (pintype "passive"))
      (node (ref "TH1") (pin "1") (pinfunction "1_1") (pintype "passive"))
      (node (ref "TH2") (pin "1") (pinfunction "1_1") (pintype "passive"))
      (node (ref "TH3") (pin "1") (pinfunction "1_1") (pintype "passive"))
      (node (ref "TH4") (pin "1") (pinfunction "1_1") (pintype "passive"))
      (node (ref "TH5") (pin "1") (pinfunction "1_1") (pintype "passive"))
      (node (ref "TH6") (pin "1") (pinfunction "1_1") (pintype "passive"))
      (node (ref "U19") (pin "1") (pinfunction "GND_1") (pintype "power_in"))
    )
    (net (code "27") (name "Net-(R113-Pad1)") (class "Default")
      (node (ref "R113") (pin "1") (pinfunction "1_1") (pintype "passive"))
      (node (ref "R114") (pin "1") (pinfunction "1_1") (pintype "passive"))
      (node (ref "R115") (pin "2") (pinfunction "2_2") (pintype "passive"))
    )
    (net (code "28") (name "Net-(R124-Pad1)") (class "Default")
      (node (ref "R124") (pin "1") (pinfunction "1_1") (pintype "passive"))
      (node (ref "R125") (pin "1") (pinfunction "1_1") (pintype "passive"))
      (node (ref "R126") (pin "2") (pinfunction "2_2") (pintype "passive"))
    )
    (net (code "29") (name "Net-(R132-Pad1)") (class "Default")
      (node (ref "R132") (pin "1") (pinfunction "1_1") (pintype "passive"))
      (node (ref "R134") (pin "1") (pinfunction "1_1") (pintype "passive"))
      (node (ref "R135") (pin "2") (pinfunction "2_2") (pintype "passive"))
    )
    (net (code "30") (name "Net-(U19-SCL)") (class "Default")
      (node (ref "R127") (pin "2") (pinfunction "2_2") (pintype "passive"))
      (node (ref "R133") (pin "2") (pinfunction "2_2") (pintype "passive"))
      (node (ref "U19") (pin "4") (pinfunction "SCL_4") (pintype "passive"))
    )
    (net (code "31") (name "Net-(U19-SDA)") (class "Default")
      (node (ref "R130") (pin "2") (pinfunction "2_2") (pintype "passive"))
      (node (ref "R131") (pin "2") (pinfunction "2_2") (pintype "passive"))
      (node (ref "U19") (pin "3") (pinfunction "SDA_3") (pintype "passive"))
    )
    (net (code "32") (name "V-POS3.3V") (class "Default")
      (node (ref "C48") (pin "1") (pinfunction "1_1") (pintype "passive"))
      (node (ref "U19") (pin "2") (pinfunction "VSS_2") (pintype "power_in"))
    )
    (net (code "33") (name "V-POS5V") (class "Default")
      (node (ref "R105") (pin "2") (pinfunction "2_2") (pintype "passive"))
      (node (ref "R106") (pin "2") (pinfunction "2_2") (pintype "passive"))
      (node (ref "R107") (pin "2") (pinfunction "2_2") (pintype "passive"))
      (node (ref "R108") (pin "2") (pinfunction "2_2") (pintype "passive"))
      (node (ref "R116") (pin "2") (pinfunction "2_2") (pintype "passive"))
      (node (ref "R117") (pin "2") (pinfunction "2_2") (pintype "passive"))
      (node (ref "R118") (pin "2") (pinfunction "2_2") (pintype "passive"))
      (node (ref "R120") (pin "2") (pinfunction "2_2") (pintype "passive"))
      (node (ref "R128") (pin "2") (pinfunction "2_2") (pintype "passive"))
    )
    (net (code "34") (name "V-POS12V") (class "Default")
      (node (ref "R109") (pin "2") (pinfunction "2_2") (pintype "passive"))
      (node (ref "R121") (pin "2") (pinfunction "2_2") (pintype "passive"))
      (node (ref "R129") (pin "2") (pinfunction "2_2") (pintype "passive"))
    )
  )
)
